# attinier85-batty-shield-mk-2_2.net
KiCad netlist of a schematic drawn in EAGLE
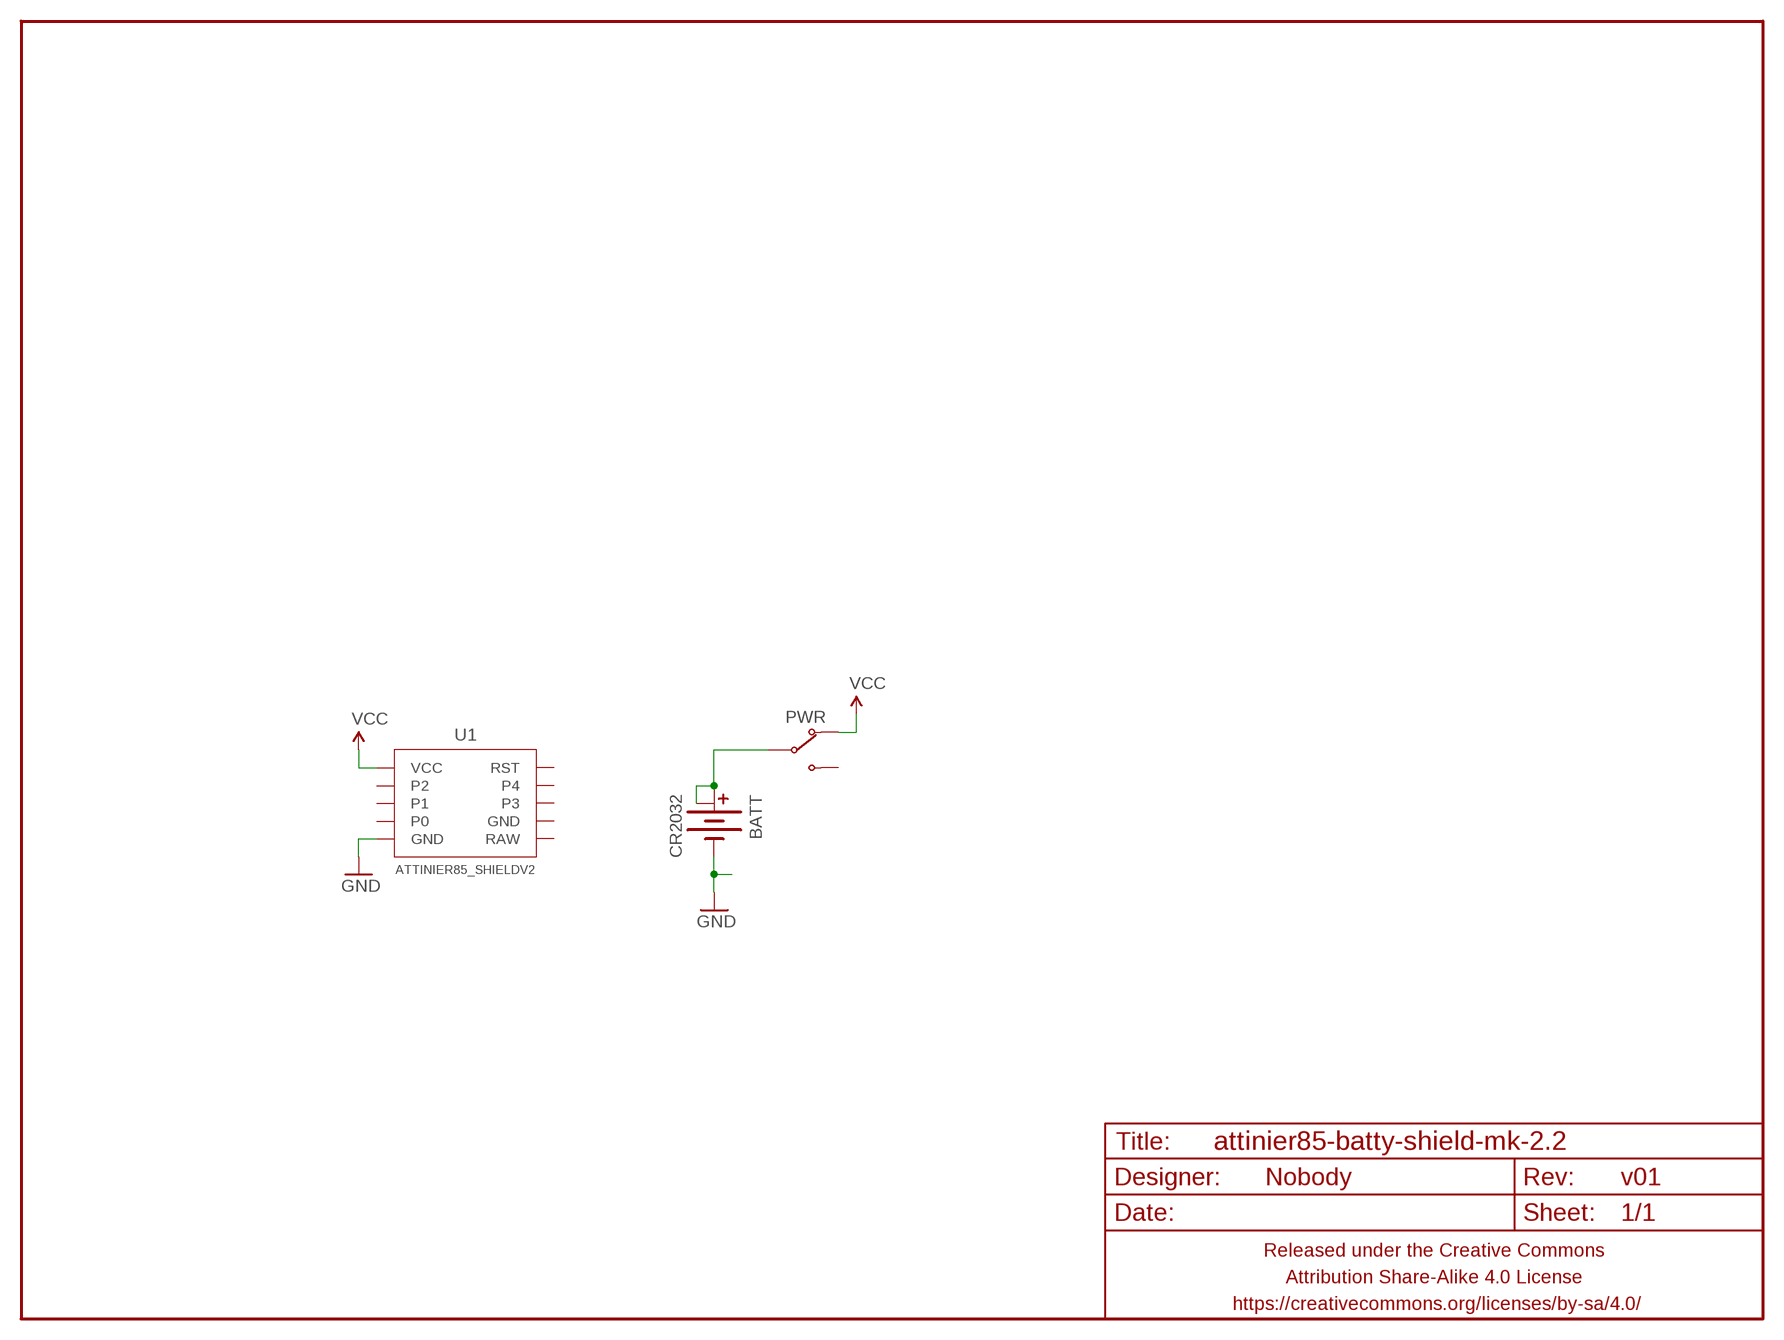
[diagram p0: schematic, sheet 1]

(export (version "E")
  (design (tool "Eeschema 10.0.6"))
  (components
    (comp (ref "BATT")
      (value "CR2032")
      (footprint "eagle-import:BATTCON_20MM_MINE")
      (libsource (lib "eagle-import") (part "BATTERY-COINCR2032_SMD"))
    )
    (comp (ref "FRAME1")
      (value "FRAME-LETTERNO_PACKAGE")
      (footprint "eagle-import:DUMMY")
      (fields (field (name "DESIGNER") "Nobody"))
      (libsource (lib "eagle-import") (part "FRAME-LETTERNO_PACKAGE"))
    )
    (comp (ref "PWR")
      (value "SWITCH-SPDTPTH-RA-2MM")
      (footprint "eagle-import:SPDT-RA-2MM")
      (libsource (lib "eagle-import") (part "SWITCH-SPDTPTH-RA-2MM"))
    )
    (comp (ref "U1")
      (value "ATTINIER85_SHIELDV2")
      (footprint "eagle-import:ATTINIER85_SHIELD_V2")
      (libsource (lib "eagle-import") (part "ATTINIER85_SHIELDV2"))
    )
  )
  (nets
    (net (code "1") (name "GND") (class "Default")
      (node (ref "BATT") (pin "BOTTOM") (pinfunction "-_BOTTOM") (pintype "bidirectional"))
      (node (ref "U1") (pin "GND@2") (pinfunction "GND_GND@2") (pintype "bidirectional"))
    )
    (net (code "2") (name "Net-(BATT-+)") (class "Default")
      (node (ref "BATT") (pin "TOP@1") (pinfunction "+_TOP@1") (pintype "bidirectional"))
      (node (ref "BATT") (pin "TOP@2") (pinfunction "+1_TOP@2") (pintype "bidirectional"))
      (node (ref "PWR") (pin "2") (pinfunction "COM_2") (pintype "passive"))
    )
    (net (code "3") (name "VCC") (class "Default")
      (node (ref "PWR") (pin "1") (pinfunction "NC_1") (pintype "passive"))
      (node (ref "U1") (pin "VCC") (pinfunction "VCC_VCC") (pintype "bidirectional"))
    )
    (net (code "4") (name "unconnected-(PWR-NO-Pad3)") (class "Default")
      (node (ref "PWR") (pin "3") (pinfunction "NO_3") (pintype "passive"))
    )
    (net (code "5") (name "unconnected-(U1-GND-PadGND@1)") (class "Default")
      (node (ref "U1") (pin "GND@1") (pinfunction "GND_GND@1") (pintype "bidirectional"))
    )
    (net (code "6") (name "unconnected-(U1-P0-Pad0)") (class "Default")
      (node (ref "U1") (pin "0") (pinfunction "P0_0") (pintype "bidirectional"))
    )
    (net (code "7") (name "unconnected-(U1-P1-Pad1)") (class "Default")
      (node (ref "U1") (pin "1") (pinfunction "P1_1") (pintype "bidirectional"))
    )
    (net (code "8") (name "unconnected-(U1-P2-Pad2)") (class "Default")
      (node (ref "U1") (pin "2") (pinfunction "P2_2") (pintype "bidirectional"))
    )
    (net (code "9") (name "unconnected-(U1-P3-Pad3)") (class "Default")
      (node (ref "U1") (pin "3") (pinfunction "P3_3") (pintype "bidirectional"))
    )
    (net (code "10") (name "unconnected-(U1-P4-Pad4)") (class "Default")
      (node (ref "U1") (pin "4") (pinfunction "P4_4") (pintype "bidirectional"))
    )
    (net (code "11") (name "unconnected-(U1-PadRAW)") (class "Default")
      (node (ref "U1") (pin "RAW") (pinfunction "RAW_RAW") (pintype "bidirectional"))
    )
    (net (code "12") (name "unconnected-(U1-PadRST)") (class "Default")
      (node (ref "U1") (pin "RST") (pinfunction "RST_RST") (pintype "bidirectional"))
    )
  )
)
